# PF5b_Filter2A.net
KiCad netlist of a schematic drawn in Altium Designer
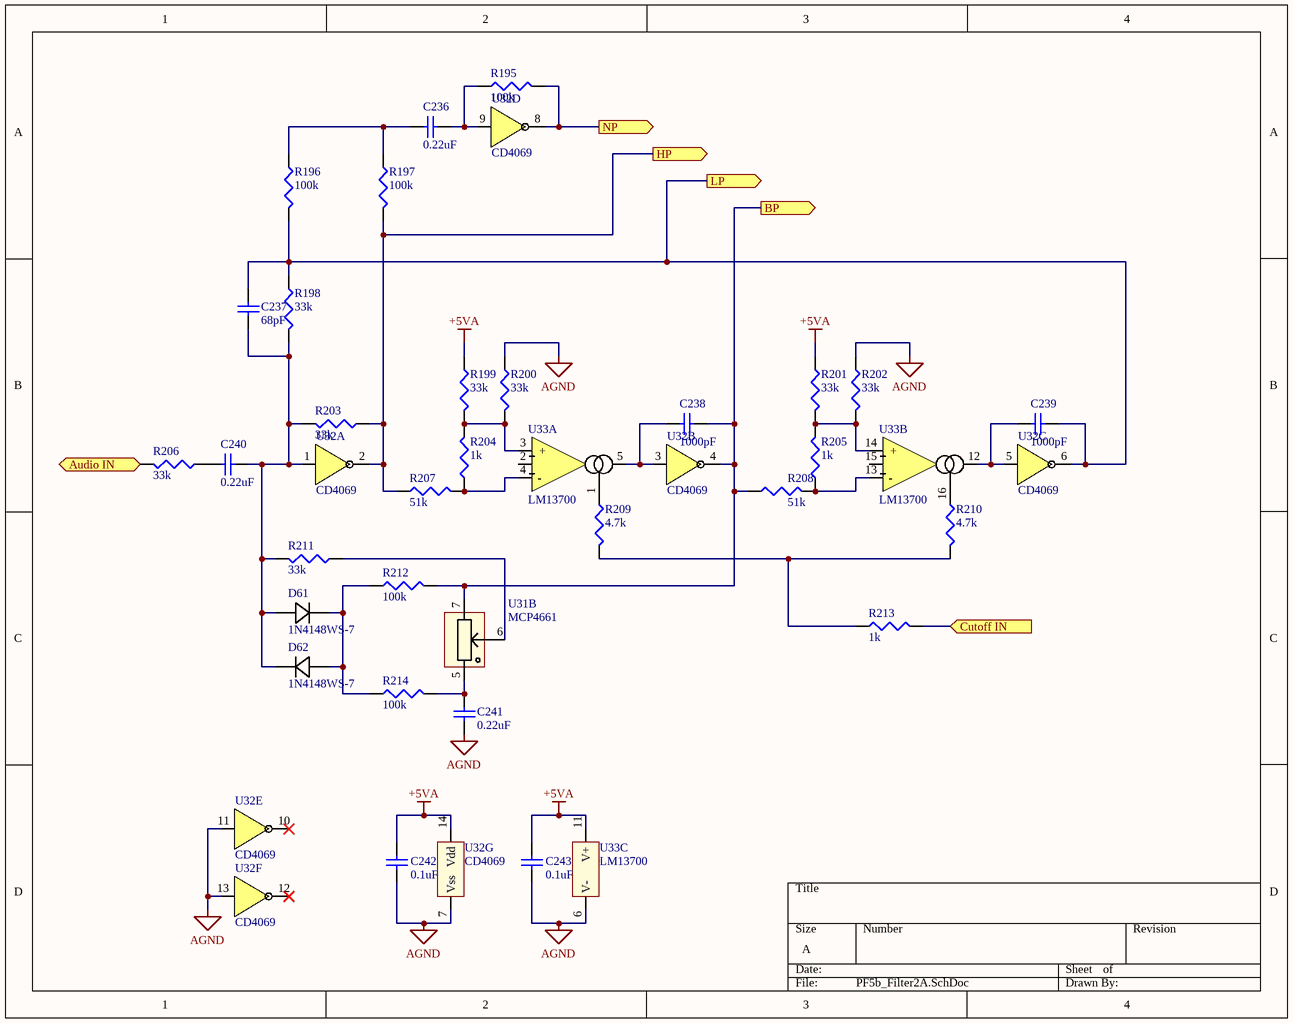
[diagram p0: PF5b_Filter2A.SchDoc]

(export (version "E")
  (design (tool "Eeschema 10.0.6"))
  (components
    (comp (ref "C236")
      (value "0.22uF")
      (footprint "CAPC1608X08")
      (description "Capacitor (Semiconductor SIM Model)")
      (libsource (lib "Michel") (part "Cap Semi"))
    )
    (comp (ref "C237")
      (value "68pF")
      (footprint "CAPC1608X08")
      (description "Capacitor (Semiconductor SIM Model)")
      (libsource (lib "Michel") (part "Cap Semi"))
    )
    (comp (ref "C238")
      (value "1000pF")
      (footprint "CAPC1608X08")
      (description "Capacitor (Semiconductor SIM Model)")
      (libsource (lib "Michel") (part "Cap Semi"))
    )
    (comp (ref "C239")
      (value "1000pF")
      (footprint "CAPC1608X08")
      (description "Capacitor (Semiconductor SIM Model)")
      (libsource (lib "Michel") (part "Cap Semi"))
    )
    (comp (ref "C240")
      (value "0.22uF")
      (footprint "CAPC1608X08")
      (description "Capacitor (Semiconductor SIM Model)")
      (libsource (lib "Michel") (part "Cap Semi"))
    )
    (comp (ref "C241")
      (value "0.22uF")
      (footprint "CAPC1608X08")
      (description "Capacitor (Semiconductor SIM Model)")
      (libsource (lib "Michel") (part "Cap Semi"))
    )
    (comp (ref "C242")
      (value "0.1uF")
      (footprint "CAPC1608X08")
      (description "Capacitor (Semiconductor SIM Model)")
      (libsource (lib "Michel") (part "Cap Semi"))
    )
    (comp (ref "C243")
      (value "0.1uF")
      (footprint "CAPC1608X08")
      (description "Capacitor (Semiconductor SIM Model)")
      (libsource (lib "Michel") (part "Cap Semi"))
    )
    (comp (ref "D61")
      (value "1N4148WS-7")
      (footprint "SOD323-M")
      (description "Diode signaux faibles")
      (libsource (lib "Michel") (part "1N4148WS-7"))
    )
    (comp (ref "D62")
      (value "1N4148WS-7")
      (footprint "SOD323-M")
      (description "Diode signaux faibles")
      (libsource (lib "Michel") (part "1N4148WS-7"))
    )
    (comp (ref "R195")
      (value "100k")
      (footprint "RESC1608X05")
      (description "Resistor")
      (libsource (lib "Michel") (part "Res3"))
    )
    (comp (ref "R196")
      (value "100k")
      (footprint "RESC1608X05")
      (description "Resistor")
      (libsource (lib "Michel") (part "Res3"))
    )
    (comp (ref "R197")
      (value "100k")
      (footprint "RESC1608X05")
      (description "Resistor")
      (libsource (lib "Michel") (part "Res3"))
    )
    (comp (ref "R198")
      (value "33k")
      (footprint "RESC1608X05")
      (description "Resistor")
      (libsource (lib "Michel") (part "Res3"))
    )
    (comp (ref "R199")
      (value "33k")
      (footprint "RESC1608X05")
      (description "Resistor")
      (libsource (lib "Michel") (part "Res3"))
    )
    (comp (ref "R200")
      (value "33k")
      (footprint "RESC1608X05")
      (description "Resistor")
      (libsource (lib "Michel") (part "Res3"))
    )
    (comp (ref "R201")
      (value "33k")
      (footprint "RESC1608X05")
      (description "Resistor")
      (libsource (lib "Michel") (part "Res3"))
    )
    (comp (ref "R202")
      (value "33k")
      (footprint "RESC1608X05")
      (description "Resistor")
      (libsource (lib "Michel") (part "Res3"))
    )
    (comp (ref "R203")
      (value "33k")
      (footprint "RESC1608X05")
      (description "Resistor")
      (libsource (lib "Michel") (part "Res3"))
    )
    (comp (ref "R204")
      (value "1k")
      (footprint "RESC1608X05")
      (description "Resistor")
      (libsource (lib "Michel") (part "Res3"))
    )
    (comp (ref "R205")
      (value "1k")
      (footprint "RESC1608X05")
      (description "Resistor")
      (libsource (lib "Michel") (part "Res3"))
    )
    (comp (ref "R206")
      (value "33k")
      (footprint "RESC1608X05")
      (description "Resistor")
      (libsource (lib "Michel") (part "Res3"))
    )
    (comp (ref "R207")
      (value "51k")
      (footprint "RESC1608X05")
      (description "Resistor")
      (libsource (lib "Michel") (part "Res3"))
    )
    (comp (ref "R208")
      (value "51k")
      (footprint "RESC1608X05")
      (description "Resistor")
      (libsource (lib "Michel") (part "Res3"))
    )
    (comp (ref "R209")
      (value "4.7k")
      (footprint "RESC1608X05")
      (description "Resistor")
      (libsource (lib "Michel") (part "Res3"))
    )
    (comp (ref "R210")
      (value "4.7k")
      (footprint "RESC1608X05")
      (description "Resistor")
      (libsource (lib "Michel") (part "Res3"))
    )
    (comp (ref "R211")
      (value "33k")
      (footprint "RESC1608X05")
      (description "Resistor")
      (libsource (lib "Michel") (part "Res3"))
    )
    (comp (ref "R212")
      (value "100k")
      (footprint "RESC1608X05")
      (description "Resistor")
      (libsource (lib "Michel") (part "Res3"))
    )
    (comp (ref "R213")
      (value "1k")
      (footprint "RESC1608X05")
      (description "Resistor")
      (libsource (lib "Michel") (part "Res3"))
    )
    (comp (ref "R214")
      (value "100k")
      (footprint "RESC1608X05")
      (description "Resistor")
      (libsource (lib "Michel") (part "Res3"))
    )
    (comp (ref "U31")
      (value "MCP4661")
      (footprint "TSSOP14_MC-M")
      (description "Dual DigiPot non volatile I2C")
      (libsource (lib "Michel") (part "MCP4661"))
    )
    (comp (ref "U32")
      (value "CD4069")
      (footprint "D14-M")
      (description "Hex Inverter")
      (libsource (lib "Michel") (part "CD4069"))
    )
    (comp (ref "U33")
      (value "LM13700")
      (footprint "SO16NB")
      (description "Dual Transconductance OpAmp")
      (libsource (lib "Michel") (part "LM13700M"))
    )
  )
  (nets
    (net (code "1") (name "+5VA") (class "Default")
      (node (ref "C242") (pin "1") (pinfunction "1_1") (pintype "passive"))
      (node (ref "C243") (pin "1") (pinfunction "1_1") (pintype "passive"))
      (node (ref "R199") (pin "1") (pinfunction "1_1") (pintype "passive"))
      (node (ref "R201") (pin "1") (pinfunction "1_1") (pintype "passive"))
      (node (ref "U32") (pin "14") (pinfunction "Vdd_14") (pintype "power_in"))
      (node (ref "U33") (pin "11") (pinfunction "V+_11") (pintype "power_in"))
    )
    (net (code "2") (name "/Audio IN") (class "Default")
      (node (ref "R206") (pin "2") (pinfunction "2_2") (pintype "passive"))
    )
    (net (code "3") (name "/BP") (class "Default")
      (node (ref "C238") (pin "2") (pinfunction "2_2") (pintype "passive"))
      (node (ref "R208") (pin "1") (pinfunction "1_1") (pintype "passive"))
      (node (ref "R212") (pin "2") (pinfunction "2_2") (pintype "passive"))
      (node (ref "U31") (pin "7") (pinfunction "P1A_7") (pintype "passive"))
      (node (ref "U32") (pin "4") (pinfunction "~{B}_4") (pintype "passive"))
    )
    (net (code "4") (name "/Cutoff IN") (class "Default")
      (node (ref "R213") (pin "2") (pinfunction "2_2") (pintype "passive"))
    )
    (net (code "5") (name "/HP") (class "Default")
      (node (ref "R197") (pin "2") (pinfunction "2_2") (pintype "passive"))
      (node (ref "R203") (pin "1") (pinfunction "1_1") (pintype "passive"))
      (node (ref "R207") (pin "1") (pinfunction "1_1") (pintype "passive"))
      (node (ref "U32") (pin "2") (pinfunction "~{A}_2") (pintype "passive"))
    )
    (net (code "6") (name "/LP") (class "Default")
      (node (ref "C237") (pin "2") (pinfunction "2_2") (pintype "passive"))
      (node (ref "C239") (pin "2") (pinfunction "2_2") (pintype "passive"))
      (node (ref "R196") (pin "2") (pinfunction "2_2") (pintype "passive"))
      (node (ref "R198") (pin "1") (pinfunction "1_1") (pintype "passive"))
      (node (ref "U32") (pin "6") (pinfunction "~{C}_6") (pintype "passive"))
    )
    (net (code "7") (name "/NP") (class "Default")
      (node (ref "R195") (pin "2") (pinfunction "2_2") (pintype "passive"))
      (node (ref "U32") (pin "8") (pinfunction "~{D}_8") (pintype "passive"))
    )
    (net (code "8") (name "AGND") (class "Default")
      (node (ref "C241") (pin "1") (pinfunction "1_1") (pintype "passive"))
      (node (ref "C242") (pin "2") (pinfunction "2_2") (pintype "passive"))
      (node (ref "C243") (pin "2") (pinfunction "2_2") (pintype "passive"))
      (node (ref "R200") (pin "1") (pinfunction "1_1") (pintype "passive"))
      (node (ref "R202") (pin "1") (pinfunction "1_1") (pintype "passive"))
      (node (ref "U32") (pin "11") (pinfunction "E_11") (pintype "passive"))
      (node (ref "U32") (pin "13") (pinfunction "F_13") (pintype "passive"))
      (node (ref "U32") (pin "7") (pinfunction "Vss_7") (pintype "power_in"))
      (node (ref "U33") (pin "6") (pinfunction "V-_6") (pintype "power_in"))
    )
    (net (code "9") (name "Net-(C236-Pad1)") (class "Default")
      (node (ref "C236") (pin "1") (pinfunction "1_1") (pintype "passive"))
      (node (ref "R196") (pin "1") (pinfunction "1_1") (pintype "passive"))
      (node (ref "R197") (pin "1") (pinfunction "1_1") (pintype "passive"))
    )
    (net (code "10") (name "Net-(C240-Pad1)") (class "Default")
      (node (ref "C240") (pin "1") (pinfunction "1_1") (pintype "passive"))
      (node (ref "R206") (pin "1") (pinfunction "1_1") (pintype "passive"))
    )
    (net (code "11") (name "Net-(D61-Pad1)") (class "Default")
      (node (ref "D61") (pin "1") (pinfunction "1_1") (pintype "passive"))
      (node (ref "D62") (pin "2") (pinfunction "2_2") (pintype "passive"))
      (node (ref "R212") (pin "1") (pinfunction "1_1") (pintype "passive"))
      (node (ref "R214") (pin "1") (pinfunction "1_1") (pintype "passive"))
    )
    (net (code "12") (name "Net-(R209-Pad2)") (class "Default")
      (node (ref "R209") (pin "2") (pinfunction "2_2") (pintype "passive"))
      (node (ref "R210") (pin "2") (pinfunction "2_2") (pintype "passive"))
      (node (ref "R213") (pin "1") (pinfunction "1_1") (pintype "passive"))
    )
    (net (code "13") (name "Net-(U31B-P1B)") (class "Default")
      (node (ref "C241") (pin "2") (pinfunction "2_2") (pintype "passive"))
      (node (ref "R214") (pin "2") (pinfunction "2_2") (pintype "passive"))
      (node (ref "U31") (pin "5") (pinfunction "P1B_5") (pintype "passive"))
    )
    (net (code "14") (name "Net-(U31B-P1W)") (class "Default")
      (node (ref "R211") (pin "1") (pinfunction "1_1") (pintype "passive"))
      (node (ref "U31") (pin "6") (pinfunction "P1W_6") (pintype "passive"))
    )
    (net (code "15") (name "Net-(U32A-A)") (class "Default")
      (node (ref "C237") (pin "1") (pinfunction "1_1") (pintype "passive"))
      (node (ref "C240") (pin "2") (pinfunction "2_2") (pintype "passive"))
      (node (ref "D61") (pin "2") (pinfunction "2_2") (pintype "passive"))
      (node (ref "D62") (pin "1") (pinfunction "1_1") (pintype "passive"))
      (node (ref "R198") (pin "2") (pinfunction "2_2") (pintype "passive"))
      (node (ref "R203") (pin "2") (pinfunction "2_2") (pintype "passive"))
      (node (ref "R211") (pin "2") (pinfunction "2_2") (pintype "passive"))
      (node (ref "U32") (pin "1") (pinfunction "A_1") (pintype "passive"))
    )
    (net (code "16") (name "Net-(U32B-B)") (class "Default")
      (node (ref "C238") (pin "1") (pinfunction "1_1") (pintype "passive"))
      (node (ref "U32") (pin "3") (pinfunction "B_3") (pintype "passive"))
      (node (ref "U33") (pin "5") (pinfunction "OUT_5") (pintype "passive"))
    )
    (net (code "17") (name "Net-(U32C-C)") (class "Default")
      (node (ref "C239") (pin "1") (pinfunction "1_1") (pintype "passive"))
      (node (ref "U32") (pin "5") (pinfunction "C_5") (pintype "passive"))
      (node (ref "U33") (pin "12") (pinfunction "OUT_12") (pintype "passive"))
    )
    (net (code "18") (name "Net-(U32D-D)") (class "Default")
      (node (ref "C236") (pin "2") (pinfunction "2_2") (pintype "passive"))
      (node (ref "R195") (pin "1") (pinfunction "1_1") (pintype "passive"))
      (node (ref "U32") (pin "9") (pinfunction "D_9") (pintype "passive"))
    )
    (net (code "19") (name "Net-(U33A-+)") (class "Default")
      (node (ref "R199") (pin "2") (pinfunction "2_2") (pintype "passive"))
      (node (ref "R200") (pin "2") (pinfunction "2_2") (pintype "passive"))
      (node (ref "R204") (pin "2") (pinfunction "2_2") (pintype "passive"))
      (node (ref "U33") (pin "3") (pinfunction "+_3") (pintype "passive"))
    )
    (net (code "20") (name "Net-(U33A--)") (class "Default")
      (node (ref "R204") (pin "1") (pinfunction "1_1") (pintype "passive"))
      (node (ref "R207") (pin "2") (pinfunction "2_2") (pintype "passive"))
      (node (ref "U33") (pin "4") (pinfunction "-_4") (pintype "passive"))
    )
    (net (code "21") (name "Net-(U33A-BIAS)") (class "Default")
      (node (ref "R209") (pin "1") (pinfunction "1_1") (pintype "passive"))
      (node (ref "U33") (pin "1") (pinfunction "BIAS_1") (pintype "passive"))
    )
    (net (code "22") (name "Net-(U33B-+)") (class "Default")
      (node (ref "R201") (pin "2") (pinfunction "2_2") (pintype "passive"))
      (node (ref "R202") (pin "2") (pinfunction "2_2") (pintype "passive"))
      (node (ref "R205") (pin "2") (pinfunction "2_2") (pintype "passive"))
      (node (ref "U33") (pin "14") (pinfunction "+_14") (pintype "passive"))
    )
    (net (code "23") (name "Net-(U33B--)") (class "Default")
      (node (ref "R205") (pin "1") (pinfunction "1_1") (pintype "passive"))
      (node (ref "R208") (pin "2") (pinfunction "2_2") (pintype "passive"))
      (node (ref "U33") (pin "13") (pinfunction "-_13") (pintype "passive"))
    )
    (net (code "24") (name "Net-(U33B-BIAS)") (class "Default")
      (node (ref "R210") (pin "1") (pinfunction "1_1") (pintype "passive"))
      (node (ref "U33") (pin "16") (pinfunction "BIAS_16") (pintype "passive"))
    )
    (net (code "25") (name "unconnected-(U32E-~{E}-Pad10)") (class "Default")
      (node (ref "U32") (pin "10") (pinfunction "~{E}_10") (pintype "passive+no_connect"))
    )
    (net (code "26") (name "unconnected-(U32F-~{F}-Pad12)") (class "Default")
      (node (ref "U32") (pin "12") (pinfunction "~{F}_12") (pintype "passive+no_connect"))
    )
    (net (code "27") (name "unconnected-(U33A-Diode_BIAS-Pad2)") (class "Default")
      (node (ref "U33") (pin "2") (pinfunction "Diode_BIAS_2") (pintype "passive"))
    )
    (net (code "28") (name "unconnected-(U33B-Diode_BIAS-Pad15)") (class "Default")
      (node (ref "U33") (pin "15") (pinfunction "Diode_BIAS_15") (pintype "passive"))
    )
  )
)
